# medusa-ai-integrated-charger.net
KiCad netlist of a schematic drawn in Altium Designer
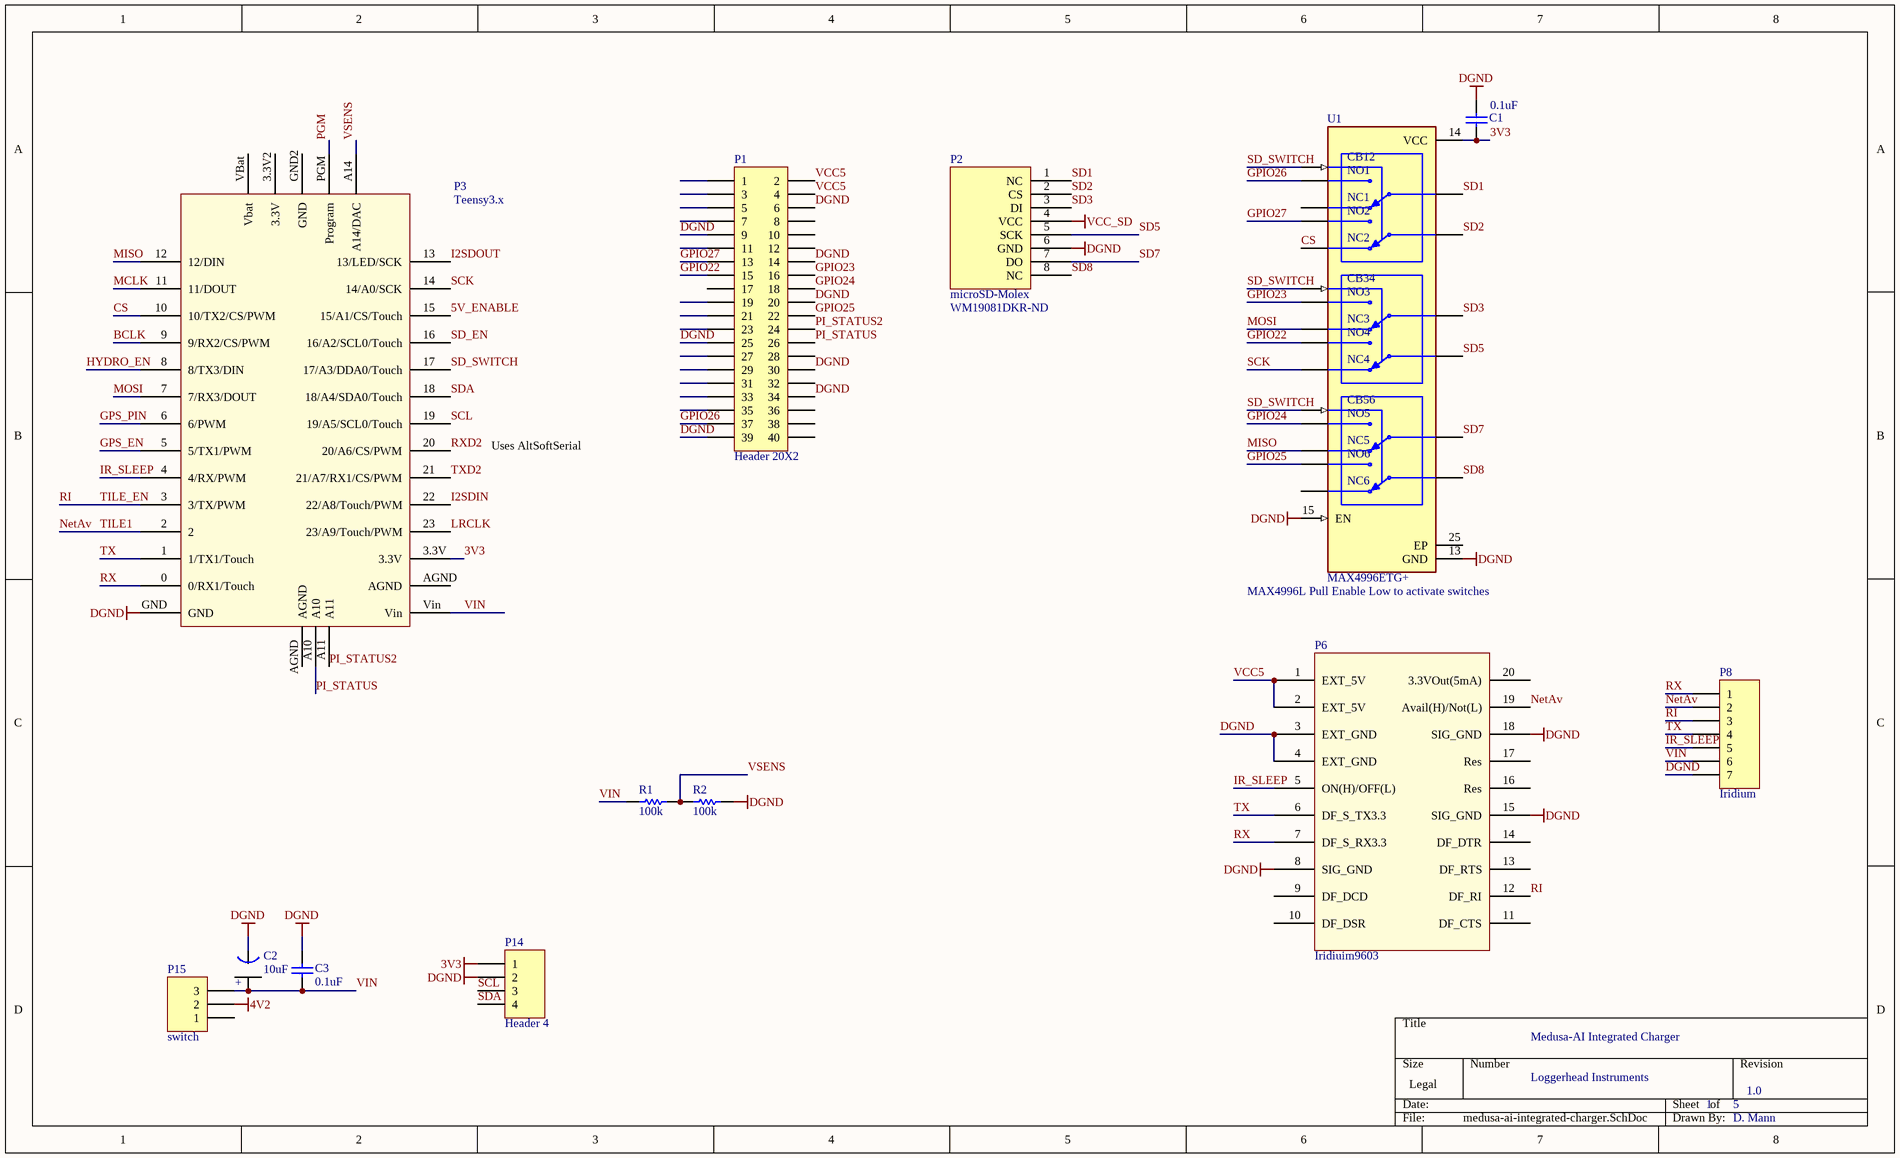
[diagram p0: medusa-ai-integrated-charger.SchDoc]

(export (version "E")
  (design (tool "Eeschema 10.0.6"))
  (components
    (comp (ref "C1")
      (value "0.1uF")
      (footprint "0402")
      (description "Ceramic Chip Capacitor - Standard")
      (fields (field (name "PUBLISHER") "Altium Limited"))
      (libsource (lib "KEMET Chip Capacitor") (part "C0402"))
    )
    (comp (ref "C2") (value "10uF") (footprint "Tant0805") (libsource (lib "Loggerhead") (part "Tant0805")))
    (comp (ref "C3")
      (value "0.1uF")
      (footprint "0402")
      (description "Ceramic Chip Capacitor - Standard")
      (fields (field (name "PUBLISHER") "Altium Limited"))
      (libsource (lib "KEMET Chip Capacitor") (part "C0402"))
    )
    (comp (ref "P1")
      (value "Header 20X2")
      (footprint "HDR2X20")
      (description "Header, 20-Pin, Dual row")
      (fields (field (name "PUBLISHER") "Altium Limited"))
      (libsource (lib "Miscellaneous Connectors") (part "Header 20X2"))
    )
    (comp (ref "P2")
      (value "microSD-Molex")
      (footprint "microSD_Molex_hinged")
      (fields (field (name "SUPPLIER PART NUMBER 1") "WM19081DKR-ND"))
      (libsource (lib "Loggerhead") (part "microSD_Molex_hinged"))
    )
    (comp (ref "P3")
      (value "Teensy3.x")
      (footprint "Teensy3.x")
      (libsource (lib "Teensy") (part "Teensy3.x"))
    )
    (comp (ref "P6")
      (value "Iridiuim9603")
      (footprint "Iridium9603")
      (libsource (lib "Loggerhead") (part "IRIDIUM9603"))
    )
    (comp (ref "P8")
      (value "Iridium")
      (footprint "HDR1X7")
      (description "Header, 7-Pin")
      (fields (field (name "PUBLISHER") "Altium Limited"))
      (libsource (lib "Miscellaneous Connectors") (part "Header 7"))
    )
    (comp (ref "P14")
      (value "Header 4")
      (footprint "HDR1X4")
      (description "Header, 4-Pin")
      (fields (field (name "PUBLISHER") "Altium Limited"))
      (libsource (lib "Miscellaneous Connectors") (part "Header 4"))
    )
    (comp (ref "P15")
      (value "switch")
      (footprint "HDR1X3")
      (description "Header, 3-Pin")
      (fields (field (name "PUBLISHER") "Altium Limited"))
      (libsource (lib "Miscellaneous Connectors") (part "Header 3"))
    )
    (comp (ref "R1")
      (value "100k")
      (footprint "3-0603")
      (fields (field (name "PUBLISHER") "Altium Limited"))
      (libsource (lib "Panasonic Resistor") (part "ERJ3RK"))
    )
    (comp (ref "R2")
      (value "100k")
      (footprint "3-0603")
      (fields (field (name "PUBLISHER") "Altium Limited"))
      (libsource (lib "Panasonic Resistor") (part "ERJ3RK"))
    )
    (comp (ref "U1")
      (value "MAX4996ETG+")
      (footprint "QFN40P350X350X80-25N")
      (description "3 Circuit IC Switch 2:2 4Ohm 24-TQFN (4x4)")
      (fields (field (name "MF") "Maxim Integrated"))
      (libsource (lib "MAX4996ETG_") (part "MAX4996ETG+"))
    )
  )
  (nets
    (net (code "1") (name "/5V_ENABLE") (class "Default")
      (node (ref "P3") (pin "15") (pinfunction "15/A1/CS/Touch_15") (pintype "passive"))
    )
    (net (code "2") (name "/BCLK") (class "Default")
      (node (ref "P3") (pin "9") (pinfunction "9/RX2/CS/PWM_9") (pintype "passive"))
    )
    (net (code "3") (name "/CS") (class "Default")
      (node (ref "P3") (pin "10") (pinfunction "10/TX2/CS/PWM_10") (pintype "passive"))
      (node (ref "U1") (pin "11") (pinfunction "NC2_11") (pintype "passive"))
    )
    (net (code "4") (name "/GPIO22") (class "Default")
      (node (ref "P1") (pin "15") (pinfunction "15_15") (pintype "passive"))
      (node (ref "U1") (pin "22") (pinfunction "NO4_22") (pintype "passive"))
    )
    (net (code "5") (name "/GPIO23") (class "Default")
      (node (ref "P1") (pin "16") (pinfunction "16_16") (pintype "passive"))
      (node (ref "U1") (pin "21") (pinfunction "NO3_21") (pintype "passive"))
    )
    (net (code "6") (name "/GPIO24") (class "Default")
      (node (ref "P1") (pin "18") (pinfunction "18_18") (pintype "passive"))
      (node (ref "U1") (pin "23") (pinfunction "NO5_23") (pintype "passive"))
    )
    (net (code "7") (name "/GPIO25") (class "Default")
      (node (ref "P1") (pin "22") (pinfunction "22_22") (pintype "passive"))
      (node (ref "U1") (pin "24") (pinfunction "NO6_24") (pintype "passive"))
    )
    (net (code "8") (name "/GPIO26") (class "Default")
      (node (ref "P1") (pin "37") (pinfunction "37_37") (pintype "passive"))
      (node (ref "U1") (pin "19") (pinfunction "NO1_19") (pintype "passive"))
    )
    (net (code "9") (name "/GPIO27") (class "Default")
      (node (ref "P1") (pin "13") (pinfunction "13_13") (pintype "passive"))
      (node (ref "U1") (pin "20") (pinfunction "NO2_20") (pintype "passive"))
    )
    (net (code "10") (name "/GPS_EN") (class "Default")
      (node (ref "P3") (pin "5") (pinfunction "5/TX1/PWM_5") (pintype "passive"))
    )
    (net (code "11") (name "/GPS_PIN") (class "Default")
      (node (ref "P3") (pin "6") (pinfunction "6/PWM_6") (pintype "passive"))
    )
    (net (code "12") (name "/HYDRO_EN") (class "Default")
      (node (ref "P3") (pin "8") (pinfunction "8/TX3/DIN_8") (pintype "passive"))
    )
    (net (code "13") (name "/I2SDIN") (class "Default")
      (node (ref "P3") (pin "22") (pinfunction "22/A8/Touch/PWM_22") (pintype "passive"))
    )
    (net (code "14") (name "/I2SDOUT") (class "Default")
      (node (ref "P3") (pin "13") (pinfunction "13/LED/SCK_13") (pintype "passive"))
    )
    (net (code "15") (name "/IR_SLEEP") (class "Default")
      (node (ref "P3") (pin "4") (pinfunction "4/RX/PWM_4") (pintype "passive"))
      (node (ref "P6") (pin "5") (pinfunction "ON(H)/OFF(L)_5") (pintype "passive"))
      (node (ref "P8") (pin "5") (pinfunction "5_5") (pintype "passive"))
    )
    (net (code "16") (name "/LRCLK") (class "Default")
      (node (ref "P3") (pin "23") (pinfunction "23/A9/Touch/PWM_23") (pintype "passive"))
    )
    (net (code "17") (name "/MCLK") (class "Default")
      (node (ref "P3") (pin "11") (pinfunction "11/DOUT_11") (pintype "passive"))
    )
    (net (code "18") (name "/MISO") (class "Default")
      (node (ref "P3") (pin "12") (pinfunction "12/DIN_12") (pintype "passive"))
      (node (ref "U1") (pin "8") (pinfunction "NC5_8") (pintype "passive"))
    )
    (net (code "19") (name "/MOSI") (class "Default")
      (node (ref "P3") (pin "7") (pinfunction "7/RX3/DOUT_7") (pintype "passive"))
      (node (ref "U1") (pin "10") (pinfunction "NC3_10") (pintype "passive"))
    )
    (net (code "20") (name "/NetAv") (class "Default")
      (node (ref "P3") (pin "2") (pinfunction "2_2") (pintype "passive"))
      (node (ref "P6") (pin "19") (pinfunction "Avail(H)/Not(L)_19") (pintype "passive"))
      (node (ref "P8") (pin "2") (pinfunction "2_2") (pintype "passive"))
    )
    (net (code "21") (name "/PGM") (class "Default")
      (node (ref "P3") (pin "PGM") (pinfunction "Program_PGM") (pintype "passive"))
    )
    (net (code "22") (name "/PI_STATUS") (class "Default")
      (node (ref "P1") (pin "26") (pinfunction "26_26") (pintype "passive"))
      (node (ref "P3") (pin "A10") (pinfunction "A10_A10") (pintype "passive"))
    )
    (net (code "23") (name "/PI_STATUS2") (class "Default")
      (node (ref "P1") (pin "24") (pinfunction "24_24") (pintype "passive"))
      (node (ref "P3") (pin "A11") (pinfunction "A11_A11") (pintype "passive"))
    )
    (net (code "24") (name "/RI") (class "Default")
      (node (ref "P3") (pin "3") (pinfunction "3/TX/PWM_3") (pintype "passive"))
      (node (ref "P6") (pin "12") (pinfunction "DF_RI_12") (pintype "passive"))
      (node (ref "P8") (pin "3") (pinfunction "3_3") (pintype "passive"))
    )
    (net (code "25") (name "/RX") (class "Default")
      (node (ref "P3") (pin "0") (pinfunction "0/RX1/Touch_0") (pintype "passive"))
      (node (ref "P6") (pin "7") (pinfunction "DF_S_RX3.3_7") (pintype "passive"))
      (node (ref "P8") (pin "1") (pinfunction "1_1") (pintype "passive"))
    )
    (net (code "26") (name "/RXD2") (class "Default")
      (node (ref "P3") (pin "20") (pinfunction "20/A6/CS/PWM_20") (pintype "passive"))
    )
    (net (code "27") (name "/SCK") (class "Default")
      (node (ref "P3") (pin "14") (pinfunction "14/A0/SCK_14") (pintype "passive"))
      (node (ref "U1") (pin "9") (pinfunction "NC4_9") (pintype "passive"))
    )
    (net (code "28") (name "/SCL") (class "Default")
      (node (ref "P14") (pin "3") (pinfunction "3_3") (pintype "passive"))
      (node (ref "P3") (pin "19") (pinfunction "19/A5/SCL0/Touch_19") (pintype "passive"))
    )
    (net (code "29") (name "/SD1") (class "Default")
      (node (ref "P2") (pin "1") (pinfunction "NC_1") (pintype "passive"))
      (node (ref "U1") (pin "18") (pinfunction "COM1_18") (pintype "passive"))
    )
    (net (code "30") (name "/SD2") (class "Default")
      (node (ref "P2") (pin "2") (pinfunction "CS_2") (pintype "passive"))
      (node (ref "U1") (pin "17") (pinfunction "COM2_17") (pintype "passive"))
    )
    (net (code "31") (name "/SD3") (class "Default")
      (node (ref "P2") (pin "3") (pinfunction "DI_3") (pintype "passive"))
      (node (ref "U1") (pin "16") (pinfunction "COM3_16") (pintype "passive"))
    )
    (net (code "32") (name "/SD5") (class "Default")
      (node (ref "P2") (pin "5") (pinfunction "SCK_5") (pintype "passive"))
      (node (ref "U1") (pin "4") (pinfunction "COM4_4") (pintype "passive"))
    )
    (net (code "33") (name "/SD7") (class "Default")
      (node (ref "P2") (pin "7") (pinfunction "DO_7") (pintype "passive"))
      (node (ref "U1") (pin "5") (pinfunction "COM5_5") (pintype "passive"))
    )
    (net (code "34") (name "/SD8") (class "Default")
      (node (ref "P2") (pin "8") (pinfunction "NC_8") (pintype "passive"))
      (node (ref "U1") (pin "6") (pinfunction "COM6_6") (pintype "passive"))
    )
    (net (code "35") (name "/SDA") (class "Default")
      (node (ref "P14") (pin "4") (pinfunction "4_4") (pintype "passive"))
      (node (ref "P3") (pin "18") (pinfunction "18/A4/SDA0/Touch_18") (pintype "passive"))
    )
    (net (code "36") (name "/SD_EN") (class "Default")
      (node (ref "P3") (pin "16") (pinfunction "16/A2/SCL0/Touch_16") (pintype "passive"))
    )
    (net (code "37") (name "/SD_SWITCH") (class "Default")
      (node (ref "P3") (pin "17") (pinfunction "17/A3/DDA0/Touch_17") (pintype "passive"))
      (node (ref "U1") (pin "1") (pinfunction "CB12_1") (pintype "input"))
      (node (ref "U1") (pin "2") (pinfunction "CB34_2") (pintype "input"))
      (node (ref "U1") (pin "3") (pinfunction "CB56_3") (pintype "input"))
    )
    (net (code "38") (name "/TX") (class "Default")
      (node (ref "P3") (pin "1") (pinfunction "1/TX1/Touch_1") (pintype "passive"))
      (node (ref "P6") (pin "6") (pinfunction "DF_S_TX3.3_6") (pintype "passive"))
      (node (ref "P8") (pin "4") (pinfunction "4_4") (pintype "passive"))
    )
    (net (code "39") (name "/TXD2") (class "Default")
      (node (ref "P3") (pin "21") (pinfunction "21/A7/RX1/CS/PWM_21") (pintype "passive"))
    )
    (net (code "40") (name "/VCC5") (class "Default")
      (node (ref "P1") (pin "2") (pinfunction "2_2") (pintype "passive"))
      (node (ref "P1") (pin "4") (pinfunction "4_4") (pintype "passive"))
      (node (ref "P6") (pin "1") (pinfunction "EXT_5V_1") (pintype "passive"))
      (node (ref "P6") (pin "2") (pinfunction "EXT_5V_2") (pintype "passive"))
    )
    (net (code "41") (name "/VIN") (class "Default")
      (node (ref "C2") (pin "2") (pinfunction "+_2") (pintype "passive"))
      (node (ref "C3") (pin "1") (pinfunction "1_1") (pintype "passive"))
      (node (ref "P15") (pin "3") (pinfunction "3_3") (pintype "passive"))
      (node (ref "P3") (pin "Vin") (pinfunction "Vin_Vin") (pintype "passive"))
      (node (ref "P8") (pin "6") (pinfunction "6_6") (pintype "passive"))
      (node (ref "R1") (pin "2") (pinfunction "2_2") (pintype "passive"))
    )
    (net (code "42") (name "/VSENS") (class "Default")
      (node (ref "P3") (pin "A14") (pinfunction "A14/DAC_A14") (pintype "passive"))
      (node (ref "R1") (pin "1") (pinfunction "1_1") (pintype "passive"))
      (node (ref "R2") (pin "2") (pinfunction "2_2") (pintype "passive"))
    )
    (net (code "43") (name "3V3") (class "Default")
      (node (ref "C1") (pin "1") (pinfunction "1_1") (pintype "passive"))
      (node (ref "P14") (pin "1") (pinfunction "1_1") (pintype "passive"))
      (node (ref "P3") (pin "3.3V") (pinfunction "3.3V_3.3V") (pintype "passive"))
      (node (ref "U1") (pin "14") (pinfunction "VCC_14") (pintype "power_in"))
    )
    (net (code "44") (name "4V2") (class "Default")
      (node (ref "P15") (pin "2") (pinfunction "2_2") (pintype "passive"))
    )
    (net (code "45") (name "DGND") (class "Default")
      (node (ref "C1") (pin "2") (pinfunction "2_2") (pintype "passive"))
      (node (ref "C2") (pin "1") (pinfunction "GND_1") (pintype "passive"))
      (node (ref "C3") (pin "2") (pinfunction "2_2") (pintype "passive"))
      (node (ref "P1") (pin "14") (pinfunction "14_14") (pintype "passive"))
      (node (ref "P1") (pin "20") (pinfunction "20_20") (pintype "passive"))
      (node (ref "P1") (pin "25") (pinfunction "25_25") (pintype "passive"))
      (node (ref "P1") (pin "30") (pinfunction "30_30") (pintype "passive"))
      (node (ref "P1") (pin "34") (pinfunction "34_34") (pintype "passive"))
      (node (ref "P1") (pin "39") (pinfunction "39_39") (pintype "passive"))
      (node (ref "P1") (pin "6") (pinfunction "6_6") (pintype "passive"))
      (node (ref "P1") (pin "9") (pinfunction "9_9") (pintype "passive"))
      (node (ref "P14") (pin "2") (pinfunction "2_2") (pintype "passive"))
      (node (ref "P2") (pin "6") (pinfunction "GND_6") (pintype "passive"))
      (node (ref "P3") (pin "GND") (pinfunction "GND_GND") (pintype "passive"))
      (node (ref "P6") (pin "15") (pinfunction "SIG_GND_15") (pintype "passive"))
      (node (ref "P6") (pin "18") (pinfunction "SIG_GND_18") (pintype "passive"))
      (node (ref "P6") (pin "3") (pinfunction "EXT_GND_3") (pintype "passive"))
      (node (ref "P6") (pin "4") (pinfunction "EXT_GND_4") (pintype "passive"))
      (node (ref "P6") (pin "8") (pinfunction "SIG_GND_8") (pintype "passive"))
      (node (ref "P8") (pin "7") (pinfunction "7_7") (pintype "passive"))
      (node (ref "R2") (pin "1") (pinfunction "1_1") (pintype "passive"))
      (node (ref "U1") (pin "13") (pinfunction "GND_13") (pintype "power_in"))
      (node (ref "U1") (pin "15") (pinfunction "EN_15") (pintype "input"))
    )
    (net (code "46") (name "VCC_SD") (class "Default")
      (node (ref "P2") (pin "4") (pinfunction "VCC_4") (pintype "passive"))
    )
    (net (code "47") (name "unconnected-(P1-Pad1)") (class "Default")
      (node (ref "P1") (pin "1") (pinfunction "1_1") (pintype "passive"))
    )
    (net (code "48") (name "unconnected-(P1-Pad3)") (class "Default")
      (node (ref "P1") (pin "3") (pinfunction "3_3") (pintype "passive"))
    )
    (net (code "49") (name "unconnected-(P1-Pad5)") (class "Default")
      (node (ref "P1") (pin "5") (pinfunction "5_5") (pintype "passive"))
    )
    (net (code "50") (name "unconnected-(P1-Pad7)") (class "Default")
      (node (ref "P1") (pin "7") (pinfunction "7_7") (pintype "passive"))
    )
    (net (code "51") (name "unconnected-(P1-Pad8)") (class "Default")
      (node (ref "P1") (pin "8") (pinfunction "8_8") (pintype "passive"))
    )
    (net (code "52") (name "unconnected-(P1-Pad10)") (class "Default")
      (node (ref "P1") (pin "10") (pinfunction "10_10") (pintype "passive"))
    )
    (net (code "53") (name "unconnected-(P1-Pad11)") (class "Default")
      (node (ref "P1") (pin "11") (pinfunction "11_11") (pintype "passive"))
    )
    (net (code "54") (name "unconnected-(P1-Pad12)") (class "Default")
      (node (ref "P1") (pin "12") (pinfunction "12_12") (pintype "passive"))
    )
    (net (code "55") (name "unconnected-(P1-Pad17)") (class "Default")
      (node (ref "P1") (pin "17") (pinfunction "17_17") (pintype "passive"))
    )
    (net (code "56") (name "unconnected-(P1-Pad19)") (class "Default")
      (node (ref "P1") (pin "19") (pinfunction "19_19") (pintype "passive"))
    )
    (net (code "57") (name "unconnected-(P1-Pad21)") (class "Default")
      (node (ref "P1") (pin "21") (pinfunction "21_21") (pintype "passive"))
    )
    (net (code "58") (name "unconnected-(P1-Pad23)") (class "Default")
      (node (ref "P1") (pin "23") (pinfunction "23_23") (pintype "passive"))
    )
    (net (code "59") (name "unconnected-(P1-Pad27)") (class "Default")
      (node (ref "P1") (pin "27") (pinfunction "27_27") (pintype "passive"))
    )
    (net (code "60") (name "unconnected-(P1-Pad28)") (class "Default")
      (node (ref "P1") (pin "28") (pinfunction "28_28") (pintype "passive"))
    )
    (net (code "61") (name "unconnected-(P1-Pad29)") (class "Default")
      (node (ref "P1") (pin "29") (pinfunction "29_29") (pintype "passive"))
    )
    (net (code "62") (name "unconnected-(P1-Pad31)") (class "Default")
      (node (ref "P1") (pin "31") (pinfunction "31_31") (pintype "passive"))
    )
    (net (code "63") (name "unconnected-(P1-Pad32)") (class "Default")
      (node (ref "P1") (pin "32") (pinfunction "32_32") (pintype "passive"))
    )
    (net (code "64") (name "unconnected-(P1-Pad33)") (class "Default")
      (node (ref "P1") (pin "33") (pinfunction "33_33") (pintype "passive"))
    )
    (net (code "65") (name "unconnected-(P1-Pad35)") (class "Default")
      (node (ref "P1") (pin "35") (pinfunction "35_35") (pintype "passive"))
    )
    (net (code "66") (name "unconnected-(P1-Pad36)") (class "Default")
      (node (ref "P1") (pin "36") (pinfunction "36_36") (pintype "passive"))
    )
    (net (code "67") (name "unconnected-(P1-Pad38)") (class "Default")
      (node (ref "P1") (pin "38") (pinfunction "38_38") (pintype "passive"))
    )
    (net (code "68") (name "unconnected-(P1-Pad40)") (class "Default")
      (node (ref "P1") (pin "40") (pinfunction "40_40") (pintype "passive"))
    )
    (net (code "69") (name "unconnected-(P3-3.3V-Pad3.3V2)") (class "Default")
      (node (ref "P3") (pin "3.3V2") (pinfunction "3.3V_3.3V2") (pintype "passive"))
    )
    (net (code "70") (name "unconnected-(P3-GND-PadGND2)") (class "Default")
      (node (ref "P3") (pin "GND2") (pinfunction "GND_GND2") (pintype "passive"))
    )
    (net (code "71") (name "unconnected-(P3-PadAGND)") (class "Default")
      (node (ref "P3") (pin "AGND") (pinfunction "AGND_AGND") (pintype "passive"))
    )
    (net (code "72") (name "unconnected-(P3-PadAGND)_1") (class "Default")
      (node (ref "P3") (pin "AGND") (pinfunction "AGND_AGND") (pintype "passive"))
    )
    (net (code "73") (name "unconnected-(P3-Vbat-PadVBat)") (class "Default")
      (node (ref "P3") (pin "VBat") (pinfunction "Vbat_VBat") (pintype "passive"))
    )
    (net (code "74") (name "unconnected-(P6-3.3VOut(5mA)-Pad20)") (class "Default")
      (node (ref "P6") (pin "20") (pinfunction "3.3VOut(5mA)_20") (pintype "passive"))
    )
    (net (code "75") (name "unconnected-(P6-DF_CTS-Pad11)") (class "Default")
      (node (ref "P6") (pin "11") (pinfunction "DF_CTS_11") (pintype "passive"))
    )
    (net (code "76") (name "unconnected-(P6-DF_DCD-Pad9)") (class "Default")
      (node (ref "P6") (pin "9") (pinfunction "DF_DCD_9") (pintype "passive"))
    )
    (net (code "77") (name "unconnected-(P6-DF_DSR-Pad10)") (class "Default")
      (node (ref "P6") (pin "10") (pinfunction "DF_DSR_10") (pintype "passive"))
    )
    (net (code "78") (name "unconnected-(P6-DF_DTR-Pad14)") (class "Default")
      (node (ref "P6") (pin "14") (pinfunction "DF_DTR_14") (pintype "passive"))
    )
    (net (code "79") (name "unconnected-(P6-DF_RTS-Pad13)") (class "Default")
      (node (ref "P6") (pin "13") (pinfunction "DF_RTS_13") (pintype "passive"))
    )
    (net (code "80") (name "unconnected-(P6-Res-Pad16)") (class "Default")
      (node (ref "P6") (pin "16") (pinfunction "Res_16") (pintype "passive"))
    )
    (net (code "81") (name "unconnected-(P6-Res-Pad17)") (class "Default")
      (node (ref "P6") (pin "17") (pinfunction "Res_17") (pintype "passive"))
    )
    (net (code "82") (name "unconnected-(P15-Pad1)") (class "Default")
      (node (ref "P15") (pin "1") (pinfunction "1_1") (pintype "passive"))
    )
    (net (code "83") (name "unconnected-(U1-EP-Pad25)") (class "Default")
      (node (ref "U1") (pin "25") (pinfunction "EP_25") (pintype "power_in"))
    )
    (net (code "84") (name "unconnected-(U1-NC1-Pad12)") (class "Default")
      (node (ref "U1") (pin "12") (pinfunction "NC1_12") (pintype "passive"))
    )
    (net (code "85") (name "unconnected-(U1-NC6-Pad7)") (class "Default")
      (node (ref "U1") (pin "7") (pinfunction "NC6_7") (pintype "passive"))
    )
  )
)
